# DM2080_BMI270.net
KiCad netlist of a schematic drawn in Altium Designer
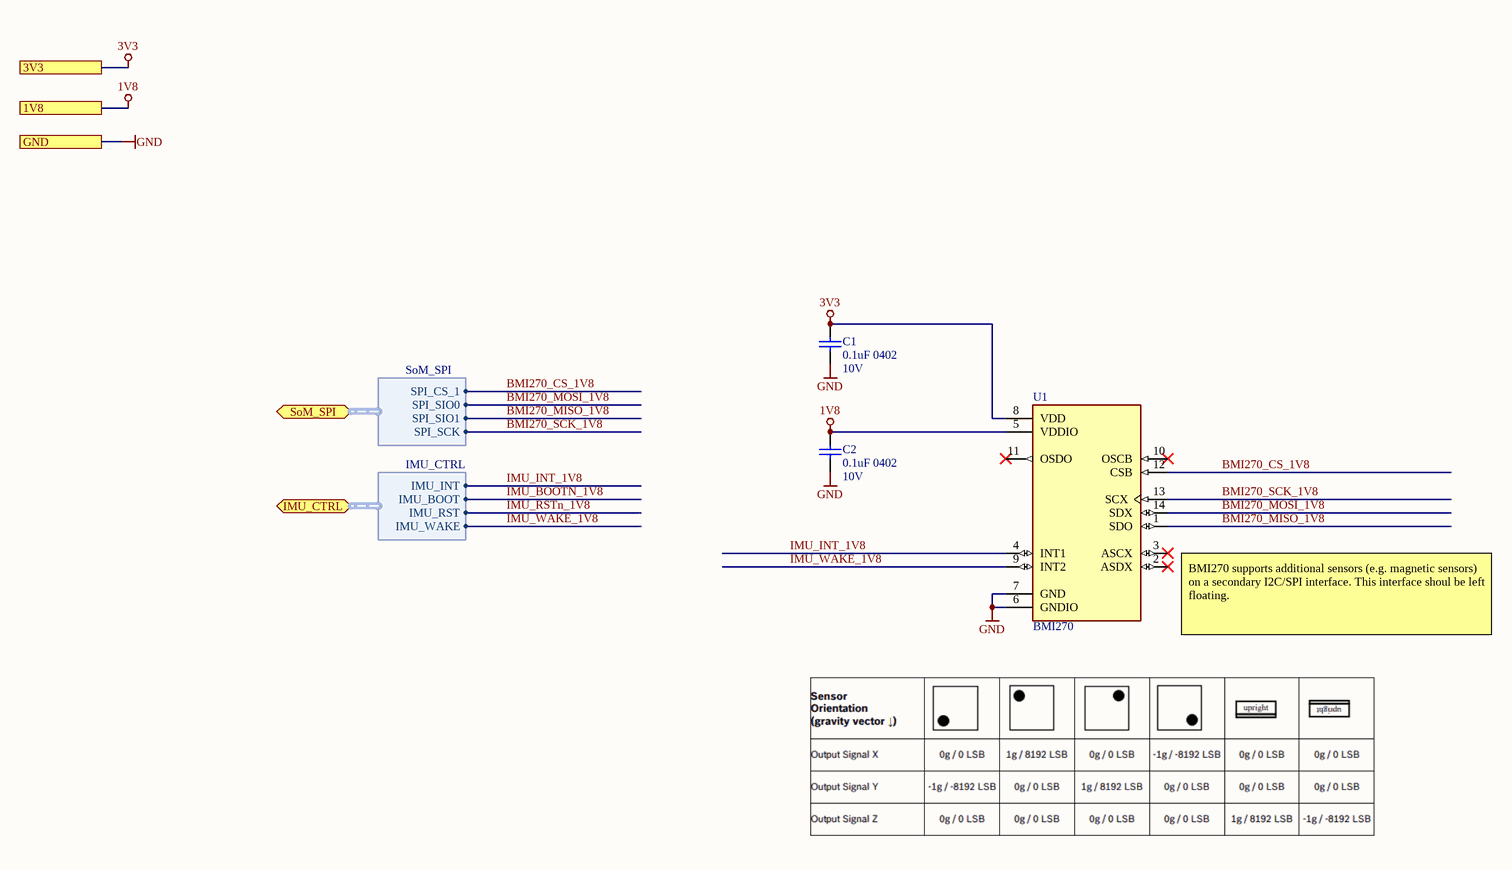
[diagram p0: DM2080_BMI270.SchDoc]

(export (version "E")
  (design (tool "Eeschema 10.0.6"))
  (components
    (comp (ref "C1")
      (value "0.1uF 0402")
      (footprint "CAP_Altium_Vault_Generic:CAPC0402(1005)70_L")
      (description "CAP CER 0.1UF 10V X7R 0402 5%")
      (fields (field (name "TOLERANCE") "5%") (field (name "VOLTAGE RATING") "10V"))
      (libsource (lib "LuxonisMaster") (part "GRM155R71A104JA01D"))
    )
    (comp (ref "C2")
      (value "0.1uF 0402")
      (footprint "CAP_Altium_Vault_Generic:CAPC0402(1005)70_L")
      (description "CAP CER 0.1UF 10V X7R 0402 5%")
      (fields (field (name "TOLERANCE") "5%") (field (name "VOLTAGE RATING") "10V"))
      (libsource (lib "LuxonisMaster") (part "GRM155R71A104JA01D"))
    )
    (comp (ref "U1")
      (value "BMI270")
      (footprint "XDCR_BMI270")
      (description "Accelerometer, Gyroscope, 6 Axis Sensor IÂ²C, SPI Output")
      (libsource (lib "DM1098LUXD-LITE") (part "BMI270"))
    )
  )
  (nets
    (net (code "3") (name "/BMI270_CS_1V8") (class "Default")
      (node (ref "U1") (pin "12") (pinfunction "CSB_12") (pintype "input"))
    )
    (net (code "4") (name "/BMI270_MISO_1V8") (class "Default")
      (node (ref "U1") (pin "1") (pinfunction "SDO_1") (pintype "bidirectional"))
    )
    (net (code "5") (name "/BMI270_MOSI_1V8") (class "Default")
      (node (ref "U1") (pin "14") (pinfunction "SDX_14") (pintype "bidirectional"))
    )
    (net (code "6") (name "/BMI270_SCK_1V8") (class "Default")
      (node (ref "U1") (pin "13") (pinfunction "SCX_13") (pintype "input"))
    )
    (net (code "8") (name "/IMU_INT_1V8") (class "Default")
      (node (ref "U1") (pin "4") (pinfunction "INT1_4") (pintype "bidirectional"))
    )
    (net (code "10") (name "/IMU_WAKE_1V8") (class "Default")
      (node (ref "U1") (pin "9") (pinfunction "INT2_9") (pintype "bidirectional"))
    )
    (net (code "13") (name "1V8") (class "Default")
      (node (ref "C2") (pin "2") (pinfunction "2_2") (pintype "passive"))
      (node (ref "U1") (pin "5") (pinfunction "VDDIO_5") (pintype "power_in"))
    )
    (net (code "14") (name "3V3") (class "Default")
      (node (ref "C1") (pin "2") (pinfunction "2_2") (pintype "passive"))
      (node (ref "U1") (pin "8") (pinfunction "VDD_8") (pintype "power_in"))
    )
    (net (code "15") (name "GND") (class "Default")
      (node (ref "C1") (pin "1") (pinfunction "1_1") (pintype "passive"))
      (node (ref "C2") (pin "1") (pinfunction "1_1") (pintype "passive"))
      (node (ref "U1") (pin "6") (pinfunction "GNDIO_6") (pintype "power_in"))
      (node (ref "U1") (pin "7") (pinfunction "GND_7") (pintype "power_in"))
    )
    (net (code "16") (name "unconnected-(U1-ASCX-Pad3)") (class "Default")
      (node (ref "U1") (pin "3") (pinfunction "ASCX_3") (pintype "bidirectional+no_connect"))
    )
    (net (code "17") (name "unconnected-(U1-ASDX-Pad2)") (class "Default")
      (node (ref "U1") (pin "2") (pinfunction "ASDX_2") (pintype "bidirectional+no_connect"))
    )
    (net (code "18") (name "unconnected-(U1-OSCB-Pad10)") (class "Default")
      (node (ref "U1") (pin "10") (pinfunction "OSCB_10") (pintype "input+no_connect"))
    )
    (net (code "19") (name "unconnected-(U1-OSDO-Pad11)") (class "Default")
      (node (ref "U1") (pin "11") (pinfunction "OSDO_11") (pintype "output+no_connect"))
    )
  )
)
